# Electrode_Breakout.net
KiCad netlist of a schematic drawn in Altium Designer
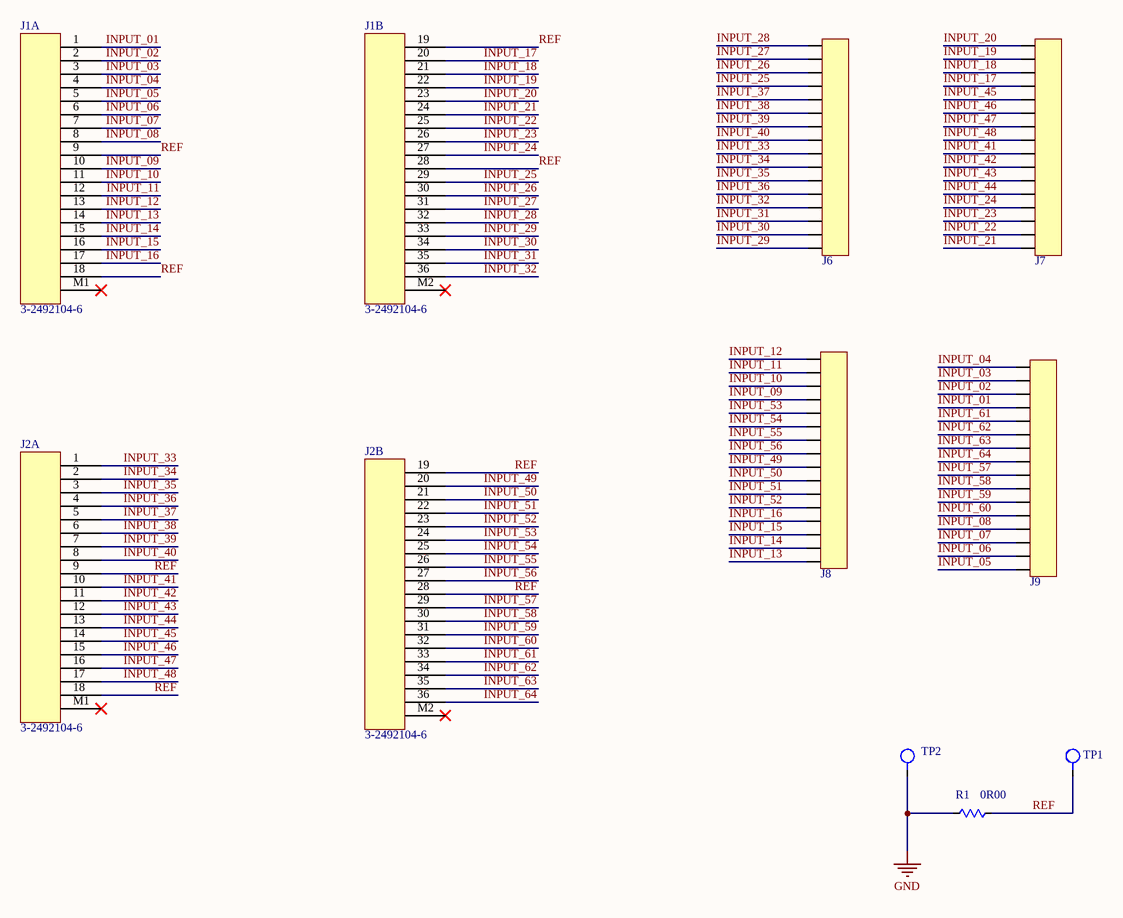
[diagram p0: Electrode_Breakout.SchDoc]

(export (version "E")
  (design (tool "Eeschema 10.0.6"))
  (components
    (comp (ref "J1")
      (value "3-2492104-6")
      (footprint "CON_ZIF_RA_36POS")
      (description "36 Position FPC Connector Contacts, Bottom 0.020\" (0.50mm) Surface Mount, Right Angle")
      (libsource (lib "UHDEMG") (part "CON_ZIF_RA_36POS"))
    )
    (comp (ref "J2")
      (value "3-2492104-6")
      (footprint "CON_ZIF_RA_36POS")
      (description "36 Position FPC Connector Contacts, Bottom 0.020\" (0.50mm) Surface Mount, Right Angle")
      (libsource (lib "UHDEMG") (part "CON_ZIF_RA_36POS"))
    )
    (comp (ref "J6")
      (value "CON_HEADER_16")
      (footprint "CON_HEADER_16")
      (libsource (lib "UHDEMG") (part "CON_HEADER_16"))
    )
    (comp (ref "J7")
      (value "CON_HEADER_16")
      (footprint "CON_HEADER_16")
      (libsource (lib "UHDEMG") (part "CON_HEADER_16"))
    )
    (comp (ref "J8")
      (value "CON_HEADER_16")
      (footprint "CON_HEADER_16")
      (libsource (lib "UHDEMG") (part "CON_HEADER_16"))
    )
    (comp (ref "J9")
      (value "CON_HEADER_16")
      (footprint "CON_HEADER_16")
      (libsource (lib "UHDEMG") (part "CON_HEADER_16"))
    )
    (comp (ref "R1")
      (value "0R00")
      (footprint "0402_Resistor")
      (description "Resistor")
      (libsource (lib "UHDEMG") (part "Resistor"))
    )
    (comp (ref "TP1")
      (value "TP_Small")
      (footprint "TP_Small_M2")
      (description "Through Hole Test Point - M2")
      (libsource (lib "UHDEMG") (part "TP_Small"))
    )
    (comp (ref "TP2")
      (value "TP_Small")
      (footprint "TP_Small_M2")
      (description "Through Hole Test Point - M2")
      (libsource (lib "UHDEMG") (part "TP_Small"))
    )
  )
  (nets
    (net (code "1") (name "/INPUT_01") (class "Default")
      (node (ref "J1") (pin "1") (pinfunction "1_1") (pintype "passive"))
      (node (ref "J9") (pin "4") (pinfunction "4_4") (pintype "passive"))
    )
    (net (code "2") (name "/INPUT_02") (class "Default")
      (node (ref "J1") (pin "2") (pinfunction "2_2") (pintype "passive"))
      (node (ref "J9") (pin "3") (pinfunction "3_3") (pintype "passive"))
    )
    (net (code "3") (name "/INPUT_03") (class "Default")
      (node (ref "J1") (pin "3") (pinfunction "3_3") (pintype "passive"))
      (node (ref "J9") (pin "2") (pinfunction "2_2") (pintype "passive"))
    )
    (net (code "4") (name "/INPUT_04") (class "Default")
      (node (ref "J1") (pin "4") (pinfunction "4_4") (pintype "passive"))
      (node (ref "J9") (pin "1") (pinfunction "1_1") (pintype "passive"))
    )
    (net (code "5") (name "/INPUT_05") (class "Default")
      (node (ref "J1") (pin "5") (pinfunction "5_5") (pintype "passive"))
      (node (ref "J9") (pin "16") (pinfunction "16_16") (pintype "passive"))
    )
    (net (code "6") (name "/INPUT_06") (class "Default")
      (node (ref "J1") (pin "6") (pinfunction "6_6") (pintype "passive"))
      (node (ref "J9") (pin "15") (pinfunction "15_15") (pintype "passive"))
    )
    (net (code "7") (name "/INPUT_07") (class "Default")
      (node (ref "J1") (pin "7") (pinfunction "7_7") (pintype "passive"))
      (node (ref "J9") (pin "14") (pinfunction "14_14") (pintype "passive"))
    )
    (net (code "8") (name "/INPUT_08") (class "Default")
      (node (ref "J1") (pin "8") (pinfunction "8_8") (pintype "passive"))
      (node (ref "J9") (pin "13") (pinfunction "13_13") (pintype "passive"))
    )
    (net (code "9") (name "/INPUT_09") (class "Default")
      (node (ref "J1") (pin "10") (pinfunction "10_10") (pintype "passive"))
      (node (ref "J8") (pin "4") (pinfunction "4_4") (pintype "passive"))
    )
    (net (code "10") (name "/INPUT_10") (class "Default")
      (node (ref "J1") (pin "11") (pinfunction "11_11") (pintype "passive"))
      (node (ref "J8") (pin "3") (pinfunction "3_3") (pintype "passive"))
    )
    (net (code "11") (name "/INPUT_11") (class "Default")
      (node (ref "J1") (pin "12") (pinfunction "12_12") (pintype "passive"))
      (node (ref "J8") (pin "2") (pinfunction "2_2") (pintype "passive"))
    )
    (net (code "12") (name "/INPUT_12") (class "Default")
      (node (ref "J1") (pin "13") (pinfunction "13_13") (pintype "passive"))
      (node (ref "J8") (pin "1") (pinfunction "1_1") (pintype "passive"))
    )
    (net (code "13") (name "/INPUT_13") (class "Default")
      (node (ref "J1") (pin "14") (pinfunction "14_14") (pintype "passive"))
      (node (ref "J8") (pin "16") (pinfunction "16_16") (pintype "passive"))
    )
    (net (code "14") (name "/INPUT_14") (class "Default")
      (node (ref "J1") (pin "15") (pinfunction "15_15") (pintype "passive"))
      (node (ref "J8") (pin "15") (pinfunction "15_15") (pintype "passive"))
    )
    (net (code "15") (name "/INPUT_15") (class "Default")
      (node (ref "J1") (pin "16") (pinfunction "16_16") (pintype "passive"))
      (node (ref "J8") (pin "14") (pinfunction "14_14") (pintype "passive"))
    )
    (net (code "16") (name "/INPUT_16") (class "Default")
      (node (ref "J1") (pin "17") (pinfunction "17_17") (pintype "passive"))
      (node (ref "J8") (pin "13") (pinfunction "13_13") (pintype "passive"))
    )
    (net (code "17") (name "/INPUT_17") (class "Default")
      (node (ref "J1") (pin "20") (pinfunction "20_20") (pintype "passive"))
      (node (ref "J7") (pin "4") (pinfunction "4_4") (pintype "passive"))
    )
    (net (code "18") (name "/INPUT_18") (class "Default")
      (node (ref "J1") (pin "21") (pinfunction "21_21") (pintype "passive"))
      (node (ref "J7") (pin "3") (pinfunction "3_3") (pintype "passive"))
    )
    (net (code "19") (name "/INPUT_19") (class "Default")
      (node (ref "J1") (pin "22") (pinfunction "22_22") (pintype "passive"))
      (node (ref "J7") (pin "2") (pinfunction "2_2") (pintype "passive"))
    )
    (net (code "20") (name "/INPUT_20") (class "Default")
      (node (ref "J1") (pin "23") (pinfunction "23_23") (pintype "passive"))
      (node (ref "J7") (pin "1") (pinfunction "1_1") (pintype "passive"))
    )
    (net (code "21") (name "/INPUT_21") (class "Default")
      (node (ref "J1") (pin "24") (pinfunction "24_24") (pintype "passive"))
      (node (ref "J7") (pin "16") (pinfunction "16_16") (pintype "passive"))
    )
    (net (code "22") (name "/INPUT_22") (class "Default")
      (node (ref "J1") (pin "25") (pinfunction "25_25") (pintype "passive"))
      (node (ref "J7") (pin "15") (pinfunction "15_15") (pintype "passive"))
    )
    (net (code "23") (name "/INPUT_23") (class "Default")
      (node (ref "J1") (pin "26") (pinfunction "26_26") (pintype "passive"))
      (node (ref "J7") (pin "14") (pinfunction "14_14") (pintype "passive"))
    )
    (net (code "24") (name "/INPUT_24") (class "Default")
      (node (ref "J1") (pin "27") (pinfunction "27_27") (pintype "passive"))
      (node (ref "J7") (pin "13") (pinfunction "13_13") (pintype "passive"))
    )
    (net (code "25") (name "/INPUT_25") (class "Default")
      (node (ref "J1") (pin "29") (pinfunction "29_29") (pintype "passive"))
      (node (ref "J6") (pin "4") (pinfunction "4_4") (pintype "passive"))
    )
    (net (code "26") (name "/INPUT_26") (class "Default")
      (node (ref "J1") (pin "30") (pinfunction "30_30") (pintype "passive"))
      (node (ref "J6") (pin "3") (pinfunction "3_3") (pintype "passive"))
    )
    (net (code "27") (name "/INPUT_27") (class "Default")
      (node (ref "J1") (pin "31") (pinfunction "31_31") (pintype "passive"))
      (node (ref "J6") (pin "2") (pinfunction "2_2") (pintype "passive"))
    )
    (net (code "28") (name "/INPUT_28") (class "Default")
      (node (ref "J1") (pin "32") (pinfunction "32_32") (pintype "passive"))
      (node (ref "J6") (pin "1") (pinfunction "1_1") (pintype "passive"))
    )
    (net (code "29") (name "/INPUT_29") (class "Default")
      (node (ref "J1") (pin "33") (pinfunction "33_33") (pintype "passive"))
      (node (ref "J6") (pin "16") (pinfunction "16_16") (pintype "passive"))
    )
    (net (code "30") (name "/INPUT_30") (class "Default")
      (node (ref "J1") (pin "34") (pinfunction "34_34") (pintype "passive"))
      (node (ref "J6") (pin "15") (pinfunction "15_15") (pintype "passive"))
    )
    (net (code "31") (name "/INPUT_31") (class "Default")
      (node (ref "J1") (pin "35") (pinfunction "35_35") (pintype "passive"))
      (node (ref "J6") (pin "14") (pinfunction "14_14") (pintype "passive"))
    )
    (net (code "32") (name "/INPUT_32") (class "Default")
      (node (ref "J1") (pin "36") (pinfunction "36_36") (pintype "passive"))
      (node (ref "J6") (pin "13") (pinfunction "13_13") (pintype "passive"))
    )
    (net (code "33") (name "/INPUT_33") (class "Default")
      (node (ref "J2") (pin "1") (pinfunction "1_1") (pintype "passive"))
      (node (ref "J6") (pin "9") (pinfunction "9_9") (pintype "passive"))
    )
    (net (code "34") (name "/INPUT_34") (class "Default")
      (node (ref "J2") (pin "2") (pinfunction "2_2") (pintype "passive"))
      (node (ref "J6") (pin "10") (pinfunction "10_10") (pintype "passive"))
    )
    (net (code "35") (name "/INPUT_35") (class "Default")
      (node (ref "J2") (pin "3") (pinfunction "3_3") (pintype "passive"))
      (node (ref "J6") (pin "11") (pinfunction "11_11") (pintype "passive"))
    )
    (net (code "36") (name "/INPUT_36") (class "Default")
      (node (ref "J2") (pin "4") (pinfunction "4_4") (pintype "passive"))
      (node (ref "J6") (pin "12") (pinfunction "12_12") (pintype "passive"))
    )
    (net (code "37") (name "/INPUT_37") (class "Default")
      (node (ref "J2") (pin "5") (pinfunction "5_5") (pintype "passive"))
      (node (ref "J6") (pin "5") (pinfunction "5_5") (pintype "passive"))
    )
    (net (code "38") (name "/INPUT_38") (class "Default")
      (node (ref "J2") (pin "6") (pinfunction "6_6") (pintype "passive"))
      (node (ref "J6") (pin "6") (pinfunction "6_6") (pintype "passive"))
    )
    (net (code "39") (name "/INPUT_39") (class "Default")
      (node (ref "J2") (pin "7") (pinfunction "7_7") (pintype "passive"))
      (node (ref "J6") (pin "7") (pinfunction "7_7") (pintype "passive"))
    )
    (net (code "40") (name "/INPUT_40") (class "Default")
      (node (ref "J2") (pin "8") (pinfunction "8_8") (pintype "passive"))
      (node (ref "J6") (pin "8") (pinfunction "8_8") (pintype "passive"))
    )
    (net (code "41") (name "/INPUT_41") (class "Default")
      (node (ref "J2") (pin "10") (pinfunction "10_10") (pintype "passive"))
      (node (ref "J7") (pin "9") (pinfunction "9_9") (pintype "passive"))
    )
    (net (code "42") (name "/INPUT_42") (class "Default")
      (node (ref "J2") (pin "11") (pinfunction "11_11") (pintype "passive"))
      (node (ref "J7") (pin "10") (pinfunction "10_10") (pintype "passive"))
    )
    (net (code "43") (name "/INPUT_43") (class "Default")
      (node (ref "J2") (pin "12") (pinfunction "12_12") (pintype "passive"))
      (node (ref "J7") (pin "11") (pinfunction "11_11") (pintype "passive"))
    )
    (net (code "44") (name "/INPUT_44") (class "Default")
      (node (ref "J2") (pin "13") (pinfunction "13_13") (pintype "passive"))
      (node (ref "J7") (pin "12") (pinfunction "12_12") (pintype "passive"))
    )
    (net (code "45") (name "/INPUT_45") (class "Default")
      (node (ref "J2") (pin "14") (pinfunction "14_14") (pintype "passive"))
      (node (ref "J7") (pin "5") (pinfunction "5_5") (pintype "passive"))
    )
    (net (code "46") (name "/INPUT_46") (class "Default")
      (node (ref "J2") (pin "15") (pinfunction "15_15") (pintype "passive"))
      (node (ref "J7") (pin "6") (pinfunction "6_6") (pintype "passive"))
    )
    (net (code "47") (name "/INPUT_47") (class "Default")
      (node (ref "J2") (pin "16") (pinfunction "16_16") (pintype "passive"))
      (node (ref "J7") (pin "7") (pinfunction "7_7") (pintype "passive"))
    )
    (net (code "48") (name "/INPUT_48") (class "Default")
      (node (ref "J2") (pin "17") (pinfunction "17_17") (pintype "passive"))
      (node (ref "J7") (pin "8") (pinfunction "8_8") (pintype "passive"))
    )
    (net (code "49") (name "/INPUT_49") (class "Default")
      (node (ref "J2") (pin "20") (pinfunction "20_20") (pintype "passive"))
      (node (ref "J8") (pin "9") (pinfunction "9_9") (pintype "passive"))
    )
    (net (code "50") (name "/INPUT_50") (class "Default")
      (node (ref "J2") (pin "21") (pinfunction "21_21") (pintype "passive"))
      (node (ref "J8") (pin "10") (pinfunction "10_10") (pintype "passive"))
    )
    (net (code "51") (name "/INPUT_51") (class "Default")
      (node (ref "J2") (pin "22") (pinfunction "22_22") (pintype "passive"))
      (node (ref "J8") (pin "11") (pinfunction "11_11") (pintype "passive"))
    )
    (net (code "52") (name "/INPUT_52") (class "Default")
      (node (ref "J2") (pin "23") (pinfunction "23_23") (pintype "passive"))
      (node (ref "J8") (pin "12") (pinfunction "12_12") (pintype "passive"))
    )
    (net (code "53") (name "/INPUT_53") (class "Default")
      (node (ref "J2") (pin "24") (pinfunction "24_24") (pintype "passive"))
      (node (ref "J8") (pin "5") (pinfunction "5_5") (pintype "passive"))
    )
    (net (code "54") (name "/INPUT_54") (class "Default")
      (node (ref "J2") (pin "25") (pinfunction "25_25") (pintype "passive"))
      (node (ref "J8") (pin "6") (pinfunction "6_6") (pintype "passive"))
    )
    (net (code "55") (name "/INPUT_55") (class "Default")
      (node (ref "J2") (pin "26") (pinfunction "26_26") (pintype "passive"))
      (node (ref "J8") (pin "7") (pinfunction "7_7") (pintype "passive"))
    )
    (net (code "56") (name "/INPUT_56") (class "Default")
      (node (ref "J2") (pin "27") (pinfunction "27_27") (pintype "passive"))
      (node (ref "J8") (pin "8") (pinfunction "8_8") (pintype "passive"))
    )
    (net (code "57") (name "/INPUT_57") (class "Default")
      (node (ref "J2") (pin "29") (pinfunction "29_29") (pintype "passive"))
      (node (ref "J9") (pin "9") (pinfunction "9_9") (pintype "passive"))
    )
    (net (code "58") (name "/INPUT_58") (class "Default")
      (node (ref "J2") (pin "30") (pinfunction "30_30") (pintype "passive"))
      (node (ref "J9") (pin "10") (pinfunction "10_10") (pintype "passive"))
    )
    (net (code "59") (name "/INPUT_59") (class "Default")
      (node (ref "J2") (pin "31") (pinfunction "31_31") (pintype "passive"))
      (node (ref "J9") (pin "11") (pinfunction "11_11") (pintype "passive"))
    )
    (net (code "60") (name "/INPUT_60") (class "Default")
      (node (ref "J2") (pin "32") (pinfunction "32_32") (pintype "passive"))
      (node (ref "J9") (pin "12") (pinfunction "12_12") (pintype "passive"))
    )
    (net (code "61") (name "/INPUT_61") (class "Default")
      (node (ref "J2") (pin "33") (pinfunction "33_33") (pintype "passive"))
      (node (ref "J9") (pin "5") (pinfunction "5_5") (pintype "passive"))
    )
    (net (code "62") (name "/INPUT_62") (class "Default")
      (node (ref "J2") (pin "34") (pinfunction "34_34") (pintype "passive"))
      (node (ref "J9") (pin "6") (pinfunction "6_6") (pintype "passive"))
    )
    (net (code "63") (name "/INPUT_63") (class "Default")
      (node (ref "J2") (pin "35") (pinfunction "35_35") (pintype "passive"))
      (node (ref "J9") (pin "7") (pinfunction "7_7") (pintype "passive"))
    )
    (net (code "64") (name "/INPUT_64") (class "Default")
      (node (ref "J2") (pin "36") (pinfunction "36_36") (pintype "passive"))
      (node (ref "J9") (pin "8") (pinfunction "8_8") (pintype "passive"))
    )
    (net (code "65") (name "/REF") (class "Default")
      (node (ref "J1") (pin "18") (pinfunction "18_18") (pintype "passive"))
      (node (ref "J1") (pin "19") (pinfunction "19_19") (pintype "passive"))
      (node (ref "J1") (pin "28") (pinfunction "28_28") (pintype "passive"))
      (node (ref "J1") (pin "9") (pinfunction "9_9") (pintype "passive"))
      (node (ref "J2") (pin "18") (pinfunction "18_18") (pintype "passive"))
      (node (ref "J2") (pin "19") (pinfunction "19_19") (pintype "passive"))
      (node (ref "J2") (pin "28") (pinfunction "28_28") (pintype "passive"))
      (node (ref "J2") (pin "9") (pinfunction "9_9") (pintype "passive"))
      (node (ref "R1") (pin "2") (pinfunction "2_2") (pintype "passive"))
      (node (ref "TP1") (pin "1") (pinfunction "1_1") (pintype "passive"))
    )
    (net (code "66") (name "GND") (class "Default")
      (node (ref "R1") (pin "1") (pinfunction "1_1") (pintype "passive"))
      (node (ref "TP2") (pin "1") (pinfunction "1_1") (pintype "passive"))
    )
    (net (code "67") (name "unconnected-(J1-PadM1)") (class "Default")
      (node (ref "J1") (pin "M1") (pinfunction "M1_M1") (pintype "passive+no_connect"))
    )
    (net (code "68") (name "unconnected-(J1-PadM2)") (class "Default")
      (node (ref "J1") (pin "M2") (pinfunction "M2_M2") (pintype "passive+no_connect"))
    )
    (net (code "69") (name "unconnected-(J2-PadM1)") (class "Default")
      (node (ref "J2") (pin "M1") (pinfunction "M1_M1") (pintype "passive+no_connect"))
    )
    (net (code "70") (name "unconnected-(J2-PadM2)") (class "Default")
      (node (ref "J2") (pin "M2") (pinfunction "M2_M2") (pintype "passive+no_connect"))
    )
  )
)
